# USB3_CON.net
KiCad netlist of a schematic drawn in Altium Designer
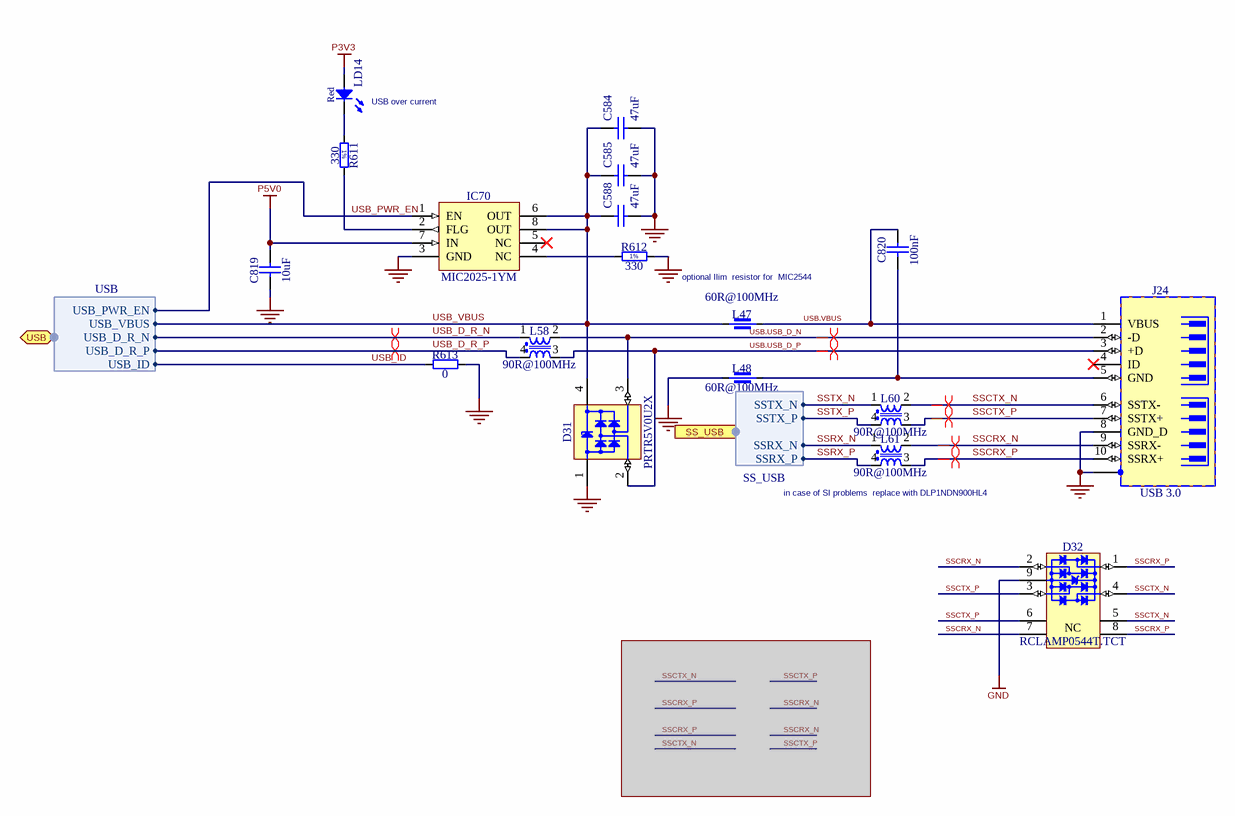
[diagram p0: USB3_CON.SchDoc]

(export (version "E")
  (design (tool "Eeschema 10.0.6"))
  (components
    (comp (ref "C584")
      (value "47uF")
      (footprint "CAPC2012X140N")
      (description "Non-polarised capacitor")
      (fields
        (field (name "MANUFACTURER PART NUMBER") "CC0805_47UF_6.3V_20%_X5R")
        (field (name "MANUFACTURER") "GENERIC")
        (field (name "AUTHOR") "CERN DEM JLC")
      )
      (libsource (lib "Capacitors") (part "Capacitor - non polarized"))
    )
    (comp (ref "C585")
      (value "47uF")
      (footprint "CAPC2012X140N")
      (description "Non-polarised capacitor")
      (fields
        (field (name "MANUFACTURER PART NUMBER") "CC0805_47UF_6.3V_20%_X5R")
        (field (name "MANUFACTURER") "GENERIC")
        (field (name "AUTHOR") "CERN DEM JLC")
      )
      (libsource (lib "Capacitors") (part "Capacitor - non polarized"))
    )
    (comp (ref "C588")
      (value "47uF")
      (footprint "CAPC2012X140N")
      (description "Non-polarised capacitor")
      (fields
        (field (name "MANUFACTURER PART NUMBER") "CC0805_47UF_6.3V_20%_X5R")
        (field (name "MANUFACTURER") "GENERIC")
        (field (name "AUTHOR") "CERN DEM JLC")
      )
      (libsource (lib "Capacitors") (part "Capacitor - non polarized"))
    )
    (comp (ref "C819")
      (value "10uF")
      (footprint "CAPC1608X87N")
      (description "Non-polarised capacitor")
      (fields
        (field (name "MANUFACTURER PART NUMBER") "CC0603_10uF_6.3V_20%_X5R")
        (field (name "MANUFACTURER") "GENERIC")
        (field (name "AUTHOR") "CERN DEM JLC")
      )
      (libsource (lib "Capacitors") (part "Capacitor - non polarized"))
    )
    (comp (ref "C820")
      (value "100nF")
      (footprint "CAPC0603X33N")
      (description "Non-polarised capacitor")
      (fields
        (field (name "MANUFACTURER PART NUMBER") "CC0201_100NF_6.3V_10%_X5R")
        (field (name "MANUFACTURER") "GENERIC")
        (field (name "AUTHOR") "CERN DEM JLC")
      )
      (libsource (lib "Capacitors") (part "Capacitor - non polarized"))
    )
    (comp (ref "D31")
      (value "PRTR5V0U2X")
      (footprint "SOT190P230X110-4N")
      (description "Ultra Low Capacitance Double Rail-to-Rail ESD Protection Diode")
      (fields
        (field (name "MANUFACTURER") "NXP SEMICONDUCTORS")
        (field (name "VOLTAGE") "5.5V")
        (field (name "AUTHOR") "CERN DEM JLC")
      )
      (libsource (lib "ICs And Semiconductors") (part "PRTR5V0U2X"))
    )
    (comp (ref "D32")
      (value "RCLAMP0544T.TCT")
      (footprint "SEMTECH_RCLAMP0544T.TCT")
      (description "Ultra Large Bandwidth HDMI ESD Protection")
      (fields
        (field (name "MANUFACTURER") "SEMTECH")
        (field (name "POWER") "75W")
        (field (name "AUTHOR") "CERN DEM MR")
      )
      (libsource (lib "ICs And Semiconductors") (part "RCLAMP0544T.TCT"))
    )
    (comp (ref "IC70")
      (value "MIC2025-1YM")
      (footprint "SOIC127P600X175-8N")
      (description "Single-Channel Power Distribution Switch MM8®")
      (fields (field (name "MANUFACTURER") "MICREL") (field (name "AUTHOR") "CERN DEM JLC"))
      (libsource (lib "ICs And Semiconductors") (part "MIC2025-1"))
    )
    (comp (ref "J24")
      (value "USB 3.0")
      (footprint "WURTH_692622030100")
      (description "10 Pin + 1 Shield Micro-USB 3.0 Type B Receptacle")
      (fields
        (field (name "PART NUMBER") "WURTH_692622030100")
        (field (name "MANUFACTURER") "WURTH ELEKTRONIK")
        (field (name "AUTHOR") "CERN DEM JLC")
      )
      (libsource (lib "Connectors") (part "Connector MicroUSB3 Type B - 10 Pin + 1 Shield"))
    )
    (comp (ref "L47")
      (value "60R@100MHz")
      (footprint "INDC4516X180N")
      (fields
        (field (name "PART NUMBER") "IND1806_MURATA_BLM41PG600SN1L")
        (field (name "POWER") "6A")
        (field (name "MANUFACTURER") "MURATA")
        (field (name "AUTHOR") "CERN DEM JLC")
      )
      (libsource (lib "Inductors & Transformers") (part "Ferrite Bead"))
    )
    (comp (ref "L48")
      (value "60R@100MHz")
      (footprint "INDC4516X180N")
      (fields
        (field (name "PART NUMBER") "IND1806_MURATA_BLM41PG600SN1L")
        (field (name "POWER") "6A")
        (field (name "MANUFACTURER") "MURATA")
        (field (name "AUTHOR") "CERN DEM JLC")
      )
      (libsource (lib "Inductors & Transformers") (part "Ferrite Bead"))
    )
    (comp (ref "L58")
      (value "90R@100MHz")
      (footprint "IND_MURATA_DLW21S")
      (description "Inductor Common Mode")
      (fields
        (field (name "MANUFACTURER PART NUMBER") "DLW21SN900SQ2L")
        (field (name "MANUFACTURER") "MURATA")
        (field (name "AUTHOR") "CERN DEM JLC")
      )
      (libsource (lib "Inductors & Transformers") (part "Inductor Common Mode 1Dot-2 4Dot-3"))
    )
    (comp (ref "L60")
      (value "90R@100MHz")
      (footprint "IND_MURATA_DLW21S")
      (description "Inductor Common Mode")
      (fields
        (field (name "MANUFACTURER PART NUMBER") "DLW21SN900SQ2L")
        (field (name "MANUFACTURER") "MURATA")
        (field (name "AUTHOR") "CERN DEM JLC")
      )
      (libsource (lib "Inductors & Transformers") (part "Inductor Common Mode 1Dot-2 4Dot-3"))
    )
    (comp (ref "L61")
      (value "90R@100MHz")
      (footprint "IND_MURATA_DLW21S")
      (description "Inductor Common Mode")
      (fields
        (field (name "MANUFACTURER PART NUMBER") "DLW21SN900SQ2L")
        (field (name "MANUFACTURER") "MURATA")
        (field (name "AUTHOR") "CERN DEM JLC")
      )
      (libsource (lib "Inductors & Transformers") (part "Inductor Common Mode 1Dot-2 4Dot-3"))
    )
    (comp (ref "LD14")
      (value "Red")
      (footprint "LED_AVAGO_HSMC-C120")
      (description "LED Red 1C 2A")
      (fields
        (field (name "MANUFACTURER PART NUMBER") "HSMC-C120")
        (field (name "MANUFACTURER") "AVAGO TECHNOLOGIES")
        (field (name "AUTHOR") "CERN DEM JMW")
      )
      (libsource (lib "ICs And Semiconductors") (part "LED Red 1C 2A"))
    )
    (comp (ref "R611")
      (value "330")
      (footprint "RESC1005X40N")
      (description "Resistor - 1%")
      (fields
        (field (name "MANUFACTURER PART NUMBER") "R0402_330R_1%_0.0625W_100PPM")
        (field (name "MANUFACTURER") "GENERIC")
        (field (name "AUTHOR") "CERN DEM JLC")
      )
      (libsource (lib "Resistors") (part "Resistor - 1%"))
    )
    (comp (ref "R612")
      (value "330")
      (footprint "RESC1005X40N")
      (description "Resistor - 1%")
      (fields
        (field (name "MANUFACTURER PART NUMBER") "R0402_330R_1%_0.0625W_100PPM")
        (field (name "MANUFACTURER") "GENERIC")
        (field (name "AUTHOR") "CERN DEM JLC")
      )
      (libsource (lib "Resistors") (part "Resistor - 1%"))
    )
    (comp (ref "R613")
      (value "0")
      (footprint "RESC1005X40N")
      (description "Resistor")
      (fields
        (field (name "MANUFACTURER PART NUMBER") "R0402_0R_JUMPER")
        (field (name "MANUFACTURER") "GENERIC")
        (field (name "AUTHOR") "CERN DEM JLC")
      )
      (libsource (lib "Resistors") (part "Resistor"))
    )
  )
  (nets
    (net (code "3") (name "/SSCRX_N") (class "Default")
      (node (ref "D32") (pin "2") (pinfunction "I/O2_2") (pintype "bidirectional"))
      (node (ref "D32") (pin "7") (pinfunction "NC_7") (pintype "passive"))
      (node (ref "J24") (pin "9") (pinfunction "SSRX-_9") (pintype "bidirectional"))
      (node (ref "L61") (pin "2") (pinfunction "2_2") (pintype "passive"))
    )
    (net (code "4") (name "/SSCRX_P") (class "Default")
      (node (ref "D32") (pin "1") (pinfunction "I/O1_1") (pintype "bidirectional"))
      (node (ref "D32") (pin "8") (pinfunction "NC_8") (pintype "passive"))
      (node (ref "J24") (pin "10") (pinfunction "SSRX+_10") (pintype "bidirectional"))
      (node (ref "L61") (pin "3") (pinfunction "3_3") (pintype "passive"))
    )
    (net (code "5") (name "/SSCTX_N") (class "Default")
      (node (ref "D32") (pin "4") (pinfunction "I/O4_4") (pintype "bidirectional"))
      (node (ref "D32") (pin "5") (pinfunction "NC_5") (pintype "passive"))
      (node (ref "J24") (pin "6") (pinfunction "SSTX-_6") (pintype "bidirectional"))
      (node (ref "L60") (pin "2") (pinfunction "2_2") (pintype "passive"))
    )
    (net (code "6") (name "/SSCTX_P") (class "Default")
      (node (ref "D32") (pin "3") (pinfunction "I/O3_3") (pintype "bidirectional"))
      (node (ref "D32") (pin "6") (pinfunction "NC_6") (pintype "passive"))
      (node (ref "J24") (pin "7") (pinfunction "SSTX+_7") (pintype "bidirectional"))
      (node (ref "L60") (pin "3") (pinfunction "3_3") (pintype "passive"))
    )
    (net (code "7") (name "/SSRX_N") (class "Default")
      (node (ref "L61") (pin "1") (pinfunction "1_1") (pintype "passive"))
    )
    (net (code "8") (name "/SSRX_P") (class "Default")
      (node (ref "L61") (pin "4") (pinfunction "4_4") (pintype "passive"))
    )
    (net (code "9") (name "/SSTX_N") (class "Default")
      (node (ref "L60") (pin "1") (pinfunction "1_1") (pintype "passive"))
    )
    (net (code "10") (name "/SSTX_P") (class "Default")
      (node (ref "L60") (pin "4") (pinfunction "4_4") (pintype "passive"))
    )
    (net (code "11") (name "/USB.USB_D_N") (class "Default")
      (node (ref "D31") (pin "3") (pinfunction "I/O2_3") (pintype "bidirectional"))
      (node (ref "J24") (pin "2") (pinfunction "-D_2") (pintype "bidirectional"))
      (node (ref "L58") (pin "2") (pinfunction "2_2") (pintype "passive"))
    )
    (net (code "12") (name "/USB.USB_D_P") (class "Default")
      (node (ref "D31") (pin "2") (pinfunction "I/O1_2") (pintype "bidirectional"))
      (node (ref "J24") (pin "3") (pinfunction "+D_3") (pintype "bidirectional"))
      (node (ref "L58") (pin "3") (pinfunction "3_3") (pintype "passive"))
    )
    (net (code "13") (name "/USB.VBUS") (class "Default")
      (node (ref "C820") (pin "2") (pinfunction "2_2") (pintype "passive"))
      (node (ref "J24") (pin "1") (pinfunction "VBUS_1") (pintype "power_in"))
      (node (ref "L47") (pin "2") (pinfunction "2_2") (pintype "passive"))
    )
    (net (code "14") (name "/USB_D_R_N") (class "Default")
      (node (ref "L58") (pin "1") (pinfunction "1_1") (pintype "passive"))
    )
    (net (code "15") (name "/USB_D_R_P") (class "Default")
      (node (ref "L58") (pin "4") (pinfunction "4_4") (pintype "passive"))
    )
    (net (code "16") (name "/USB_ID") (class "Default")
      (node (ref "R613") (pin "1") (pinfunction "1_1") (pintype "passive"))
    )
    (net (code "17") (name "/USB_PWR_EN") (class "Default")
      (node (ref "IC70") (pin "1") (pinfunction "EN_1") (pintype "input"))
    )
    (net (code "18") (name "/USB_VBUS") (class "Default")
      (node (ref "C584") (pin "2") (pinfunction "2_2") (pintype "passive"))
      (node (ref "C585") (pin "2") (pinfunction "2_2") (pintype "passive"))
      (node (ref "C588") (pin "2") (pinfunction "2_2") (pintype "passive"))
      (node (ref "D31") (pin "4") (pinfunction "VCC_4") (pintype "power_in"))
      (node (ref "IC70") (pin "6") (pinfunction "OUT_6") (pintype "power_in"))
      (node (ref "IC70") (pin "8") (pinfunction "OUT_8") (pintype "power_in"))
      (node (ref "L47") (pin "1") (pinfunction "1_1") (pintype "passive"))
    )
    (net (code "21") (name "GND") (class "Default")
      (node (ref "C584") (pin "1") (pinfunction "1_1") (pintype "passive"))
      (node (ref "C585") (pin "1") (pinfunction "1_1") (pintype "passive"))
      (node (ref "C588") (pin "1") (pinfunction "1_1") (pintype "passive"))
      (node (ref "C819") (pin "1") (pinfunction "1_1") (pintype "passive"))
      (node (ref "D31") (pin "1") (pinfunction "GND_1") (pintype "power_in"))
      (node (ref "D32") (pin "9") (pinfunction "GND_9") (pintype "power_in"))
      (node (ref "IC70") (pin "3") (pinfunction "GND_3") (pintype "power_in"))
      (node (ref "J24") (pin "11") (pinfunction "SHIELD_11") (pintype "power_in"))
      (node (ref "J24") (pin "8") (pinfunction "GND_D_8") (pintype "power_in"))
      (node (ref "L48") (pin "1") (pinfunction "1_1") (pintype "passive"))
      (node (ref "R612") (pin "2") (pinfunction "2_2") (pintype "passive"))
      (node (ref "R613") (pin "2") (pinfunction "2_2") (pintype "passive"))
    )
    (net (code "22") (name "Net-(IC70-FLG)") (class "Default")
      (node (ref "IC70") (pin "2") (pinfunction "FLG_2") (pintype "output"))
      (node (ref "R611") (pin "2") (pinfunction "2_2") (pintype "passive"))
    )
    (net (code "23") (name "Net-(IC70-NC-Pad4)") (class "Default")
      (node (ref "IC70") (pin "4") (pinfunction "NC_4") (pintype "passive"))
      (node (ref "R612") (pin "1") (pinfunction "1_1") (pintype "passive"))
    )
    (net (code "24") (name "Net-(J24-GND)") (class "Default")
      (node (ref "C820") (pin "1") (pinfunction "1_1") (pintype "passive"))
      (node (ref "J24") (pin "5") (pinfunction "GND_5") (pintype "bidirectional"))
      (node (ref "L48") (pin "2") (pinfunction "2_2") (pintype "passive"))
    )
    (net (code "25") (name "Net-(LD14-C)") (class "Default")
      (node (ref "LD14") (pin "1") (pinfunction "C_1") (pintype "passive"))
      (node (ref "R611") (pin "1") (pinfunction "1_1") (pintype "passive"))
    )
    (net (code "26") (name "P3V3") (class "Default")
      (node (ref "LD14") (pin "2") (pinfunction "A_2") (pintype "passive"))
    )
    (net (code "27") (name "P5V0") (class "Default")
      (node (ref "C819") (pin "2") (pinfunction "2_2") (pintype "passive"))
      (node (ref "IC70") (pin "7") (pinfunction "IN_7") (pintype "input"))
    )
    (net (code "28") (name "unconnected-(IC70-NC-Pad5)") (class "Default")
      (node (ref "IC70") (pin "5") (pinfunction "NC_5") (pintype "passive+no_connect"))
    )
    (net (code "29") (name "unconnected-(J24-ID-Pad4)") (class "Default")
      (node (ref "J24") (pin "4") (pinfunction "ID_4") (pintype "passive+no_connect"))
    )
  )
)
